# PWR_MGMT.net
KiCad netlist of a schematic drawn in Altium Designer
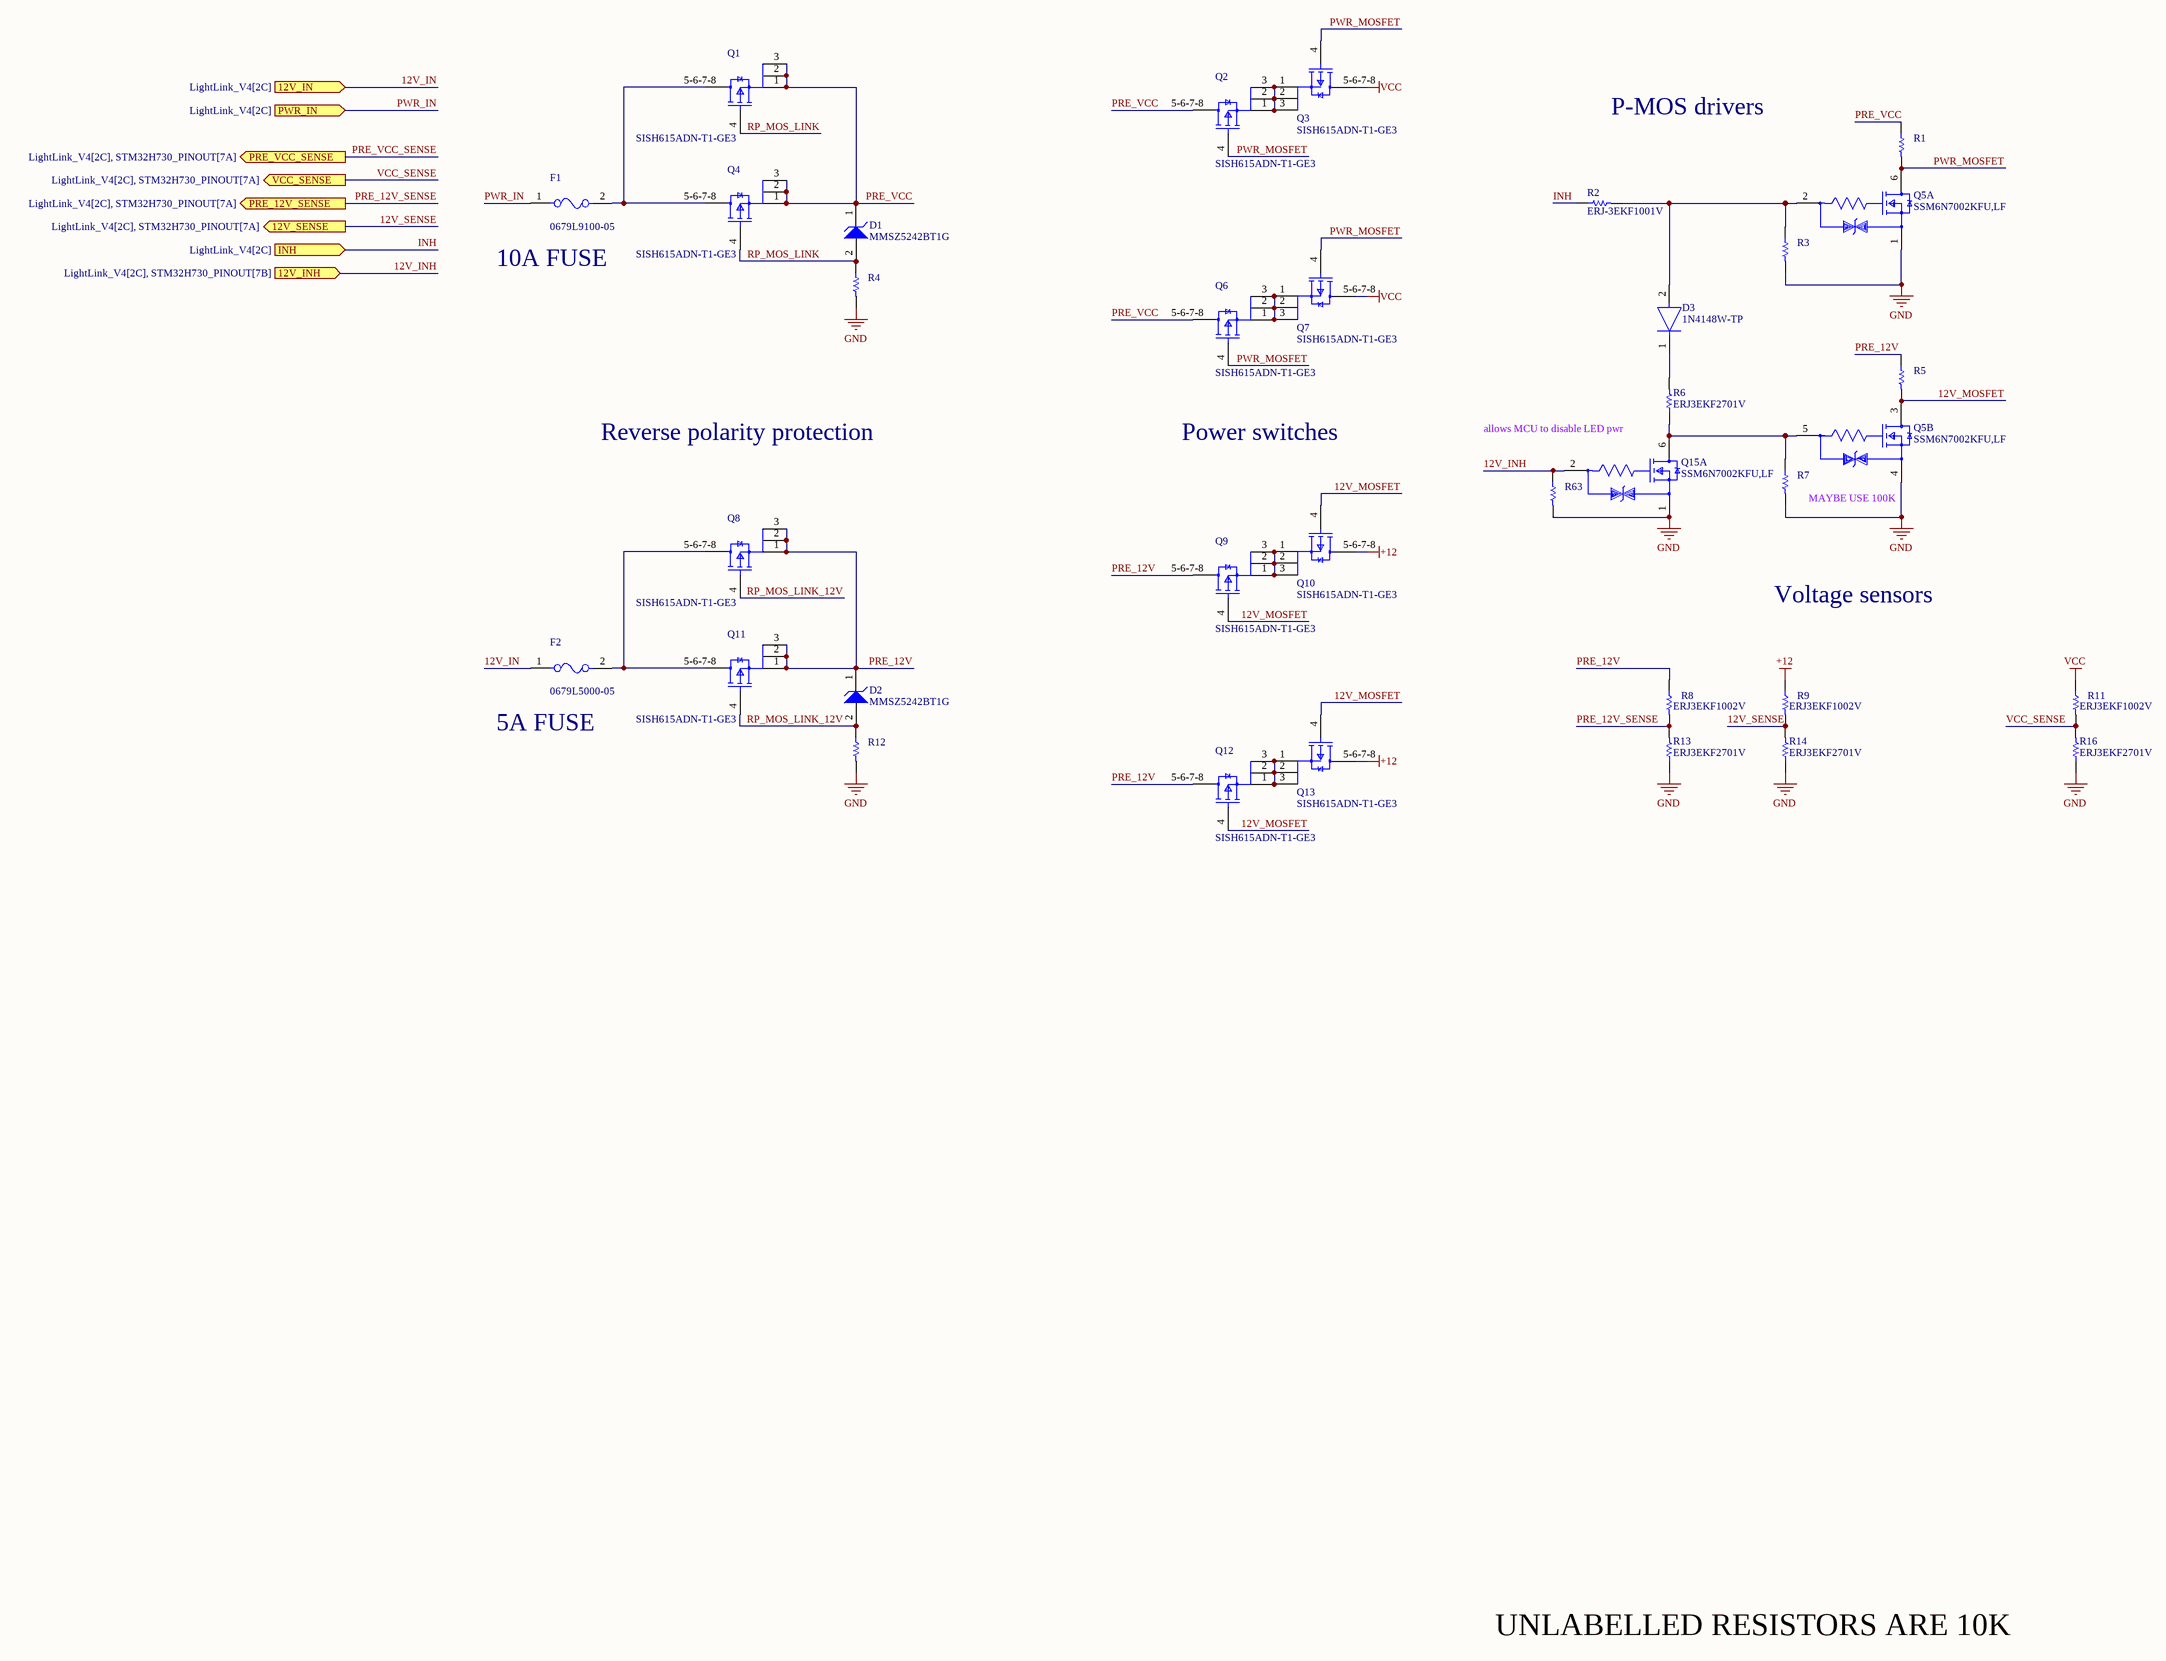
[diagram p0: PWR_MGMT.SchDoc]

(export (version "E")
  (design (tool "Eeschema 10.0.6"))
  (components
    (comp (ref "D1")
      (value "MMSZ5242BT1G")
      (footprint "ONSC-SOD-123-2-425-04_V")
      (description "Zener Voltage Regulator, 500 mW, 2-Pin SOD-123, Pb-Free, Tape and Reel")
      (fields (field (name "MANUFACTURER") "On Semiconductor"))
      (libsource (lib "Altium Content Vault") (part "ONSC-K1A2-2"))
    )
    (comp (ref "D2")
      (value "MMSZ5242BT1G")
      (footprint "ONSC-SOD-123-2-425-04_V")
      (description "Zener Voltage Regulator, 500 mW, 2-Pin SOD-123, Pb-Free, Tape and Reel")
      (fields (field (name "MANUFACTURER") "On Semiconductor"))
      (libsource (lib "Altium Content Vault") (part "ONSC-K1A2-2"))
    )
    (comp (ref "D3")
      (value "1N4148W-TP")
      (footprint "FP-SOD-123-IPC_A")
      (description "DIODE GEN PURP 100V 150MA SOD123")
      (libsource (lib "Altium Content Vault") (part "d7152d700b627762746794eb795d46e"))
    )
    (comp (ref "F1")
      (value "0679L9100-05")
      (footprint "FP-0679L-MFG")
      (description "DIFF P#!!!\r\n\r\nFUSE BRD MNT 10A 125VAC/VDC")
      (fields
        (field (name "OCTOPART") "https://octopart.com/0679l9150-01-bel+fuse-70850665")
        (field (name "MANUFACTURER") "Bel Fuse")
      )
      (libsource (lib "Altium Content Vault") (part "5bcf9b9f640e542cf0359d10258e979"))
    )
    (comp (ref "F2")
      (value "0679L5000-05")
      (footprint "FP-0679L-MFG")
      (description "DIFF P#!!!\r\n\r\nFUSE BRD MNT 5A 125VAC/VDC")
      (fields
        (field (name "OCTOPART") "https://octopart.com/0679l9150-01-bel+fuse-70850665")
        (field (name "MANUFACTURER") "Bel Fuse")
      )
      (libsource (lib "Altium Content Vault") (part "5bcf9b9f640e542cf0359d10258e979"))
    )
    (comp (ref "Q1")
      (value "SISH615ADN-T1-GE3")
      (footprint "SISH615ADN-T1-GE3-Footprint-1")
      (description "Trans MOSFET P-CH 20V 22.1A 8-Pin PowerPAK 1212 EP T/R")
      (libsource (lib "uORocketry Hardware") (part "SISH615ADN-T1-GE3-Symbol-1"))
    )
    (comp (ref "Q2")
      (value "SISH615ADN-T1-GE3")
      (footprint "SISH615ADN-T1-GE3-Footprint-1")
      (description "Trans MOSFET P-CH 20V 22.1A 8-Pin PowerPAK 1212 EP T/R")
      (libsource (lib "uORocketry Hardware") (part "SISH615ADN-T1-GE3-Symbol-1"))
    )
    (comp (ref "Q3")
      (value "SISH615ADN-T1-GE3")
      (footprint "SISH615ADN-T1-GE3-Footprint-1")
      (description "Trans MOSFET P-CH 20V 22.1A 8-Pin PowerPAK 1212 EP T/R")
      (libsource (lib "uORocketry Hardware") (part "SISH615ADN-T1-GE3-Symbol-1"))
    )
    (comp (ref "Q4")
      (value "SISH615ADN-T1-GE3")
      (footprint "SISH615ADN-T1-GE3-Footprint-1")
      (description "Trans MOSFET P-CH 20V 22.1A 8-Pin PowerPAK 1212 EP T/R")
      (libsource (lib "uORocketry Hardware") (part "SISH615ADN-T1-GE3-Symbol-1"))
    )
    (comp (ref "Q5")
      (value "SSM6N7002KFU,LF")
      (footprint "FP-SSOP6-P-0_65A-MFG")
      (description "MOSFET 2N-CH 60V 0.3A")
      (libsource (lib "Altium Content Vault") (part "088aa6ac103fdeebe0d1c52ece6b7b9"))
    )
    (comp (ref "Q6")
      (value "SISH615ADN-T1-GE3")
      (footprint "SISH615ADN-T1-GE3-Footprint-1")
      (description "Trans MOSFET P-CH 20V 22.1A 8-Pin PowerPAK 1212 EP T/R")
      (libsource (lib "uORocketry Hardware") (part "SISH615ADN-T1-GE3-Symbol-1"))
    )
    (comp (ref "Q7")
      (value "SISH615ADN-T1-GE3")
      (footprint "SISH615ADN-T1-GE3-Footprint-1")
      (description "Trans MOSFET P-CH 20V 22.1A 8-Pin PowerPAK 1212 EP T/R")
      (libsource (lib "uORocketry Hardware") (part "SISH615ADN-T1-GE3-Symbol-1"))
    )
    (comp (ref "Q8")
      (value "SISH615ADN-T1-GE3")
      (footprint "SISH615ADN-T1-GE3-Footprint-1")
      (description "Trans MOSFET P-CH 20V 22.1A 8-Pin PowerPAK 1212 EP T/R")
      (libsource (lib "uORocketry Hardware") (part "SISH615ADN-T1-GE3-Symbol-1"))
    )
    (comp (ref "Q9")
      (value "SISH615ADN-T1-GE3")
      (footprint "SISH615ADN-T1-GE3-Footprint-1")
      (description "Trans MOSFET P-CH 20V 22.1A 8-Pin PowerPAK 1212 EP T/R")
      (libsource (lib "uORocketry Hardware") (part "SISH615ADN-T1-GE3-Symbol-1"))
    )
    (comp (ref "Q10")
      (value "SISH615ADN-T1-GE3")
      (footprint "SISH615ADN-T1-GE3-Footprint-1")
      (description "Trans MOSFET P-CH 20V 22.1A 8-Pin PowerPAK 1212 EP T/R")
      (libsource (lib "uORocketry Hardware") (part "SISH615ADN-T1-GE3-Symbol-1"))
    )
    (comp (ref "Q11")
      (value "SISH615ADN-T1-GE3")
      (footprint "SISH615ADN-T1-GE3-Footprint-1")
      (description "Trans MOSFET P-CH 20V 22.1A 8-Pin PowerPAK 1212 EP T/R")
      (libsource (lib "uORocketry Hardware") (part "SISH615ADN-T1-GE3-Symbol-1"))
    )
    (comp (ref "Q12")
      (value "SISH615ADN-T1-GE3")
      (footprint "SISH615ADN-T1-GE3-Footprint-1")
      (description "Trans MOSFET P-CH 20V 22.1A 8-Pin PowerPAK 1212 EP T/R")
      (libsource (lib "uORocketry Hardware") (part "SISH615ADN-T1-GE3-Symbol-1"))
    )
    (comp (ref "Q13")
      (value "SISH615ADN-T1-GE3")
      (footprint "SISH615ADN-T1-GE3-Footprint-1")
      (description "Trans MOSFET P-CH 20V 22.1A 8-Pin PowerPAK 1212 EP T/R")
      (libsource (lib "uORocketry Hardware") (part "SISH615ADN-T1-GE3-Symbol-1"))
    )
    (comp (ref "Q15")
      (value "SSM6N7002KFU,LF")
      (footprint "FP-SSOP6-P-0_65A-MFG")
      (description "MOSFET 2N-CH 60V 0.3A")
      (libsource (lib "Altium Content Vault") (part "088aa6ac103fdeebe0d1c52ece6b7b9"))
    )
    (comp (ref "R1")
      (value "ERJ3EKF1002V")
      (footprint "RESC1609X55X30LL15T15")
      (description "Chip Resistor, 10 KOhm, +/- 1%, 0.1 W, -55 to 155 degC, 0603 (1608 Metric), RoHS, Tape and Reel")
      (fields (field (name "TOLERANCE") "1%") (field (name "MANUFACTURER") "Panasonic"))
      (libsource (lib "Altium Content Vault") (part "RES-2"))
    )
    (comp (ref "R2")
      (value "ERJ-3EKF1001V")
      (footprint "RESC1608X55X30LL15T15")
      (fields (field (name "MANUFACTURER") "Panasonic"))
      (libsource (lib "Altium Content Vault") (part "RES"))
    )
    (comp (ref "R3")
      (value "ERJ3EKF1002V")
      (footprint "RESC1609X55X30LL15T15")
      (description "Chip Resistor, 10 KOhm, +/- 1%, 0.1 W, -55 to 155 degC, 0603 (1608 Metric), RoHS, Tape and Reel")
      (fields (field (name "TOLERANCE") "1%") (field (name "MANUFACTURER") "Panasonic"))
      (libsource (lib "Altium Content Vault") (part "RES-2"))
    )
    (comp (ref "R4")
      (value "ERJ3EKF1002V")
      (footprint "RESC1609X55X30LL15T15")
      (description "Chip Resistor, 10 KOhm, +/- 1%, 0.1 W, -55 to 155 degC, 0603 (1608 Metric), RoHS, Tape and Reel")
      (fields (field (name "TOLERANCE") "1%") (field (name "MANUFACTURER") "Panasonic"))
      (libsource (lib "Altium Content Vault") (part "RES-2"))
    )
    (comp (ref "R5")
      (value "ERJ3EKF1002V")
      (footprint "RESC1609X55X30LL15T15")
      (description "Chip Resistor, 10 KOhm, +/- 1%, 0.1 W, -55 to 155 degC, 0603 (1608 Metric), RoHS, Tape and Reel")
      (fields (field (name "TOLERANCE") "1%") (field (name "MANUFACTURER") "Panasonic"))
      (libsource (lib "Altium Content Vault") (part "RES-2"))
    )
    (comp (ref "R6")
      (value "ERJ3EKF2701V")
      (footprint "RESC1608X55X30LL15T15")
      (fields (field (name "MANUFACTURER") "Panasonic"))
      (libsource (lib "Altium Content Vault") (part "RES"))
    )
    (comp (ref "R7")
      (value "ERJ3EKF1002V")
      (footprint "RESC1609X55X30LL15T15")
      (description "Chip Resistor, 10 KOhm, +/- 1%, 0.1 W, -55 to 155 degC, 0603 (1608 Metric), RoHS, Tape and Reel")
      (fields (field (name "TOLERANCE") "1%") (field (name "MANUFACTURER") "Panasonic"))
      (libsource (lib "Altium Content Vault") (part "RES-2"))
    )
    (comp (ref "R8")
      (value "ERJ3EKF1002V")
      (footprint "RESC1609X55X30LL15T15")
      (description "Chip Resistor, 10 KOhm, +/- 1%, 0.1 W, -55 to 155 degC, 0603 (1608 Metric), RoHS, Tape and Reel")
      (fields (field (name "TOLERANCE") "1%") (field (name "MANUFACTURER") "Panasonic"))
      (libsource (lib "Altium Content Vault") (part "RES-2"))
    )
    (comp (ref "R9")
      (value "ERJ3EKF1002V")
      (footprint "RESC1609X55X30LL15T15")
      (description "Chip Resistor, 10 KOhm, +/- 1%, 0.1 W, -55 to 155 degC, 0603 (1608 Metric), RoHS, Tape and Reel")
      (fields (field (name "TOLERANCE") "1%") (field (name "MANUFACTURER") "Panasonic"))
      (libsource (lib "Altium Content Vault") (part "RES-2"))
    )
    (comp (ref "R11")
      (value "ERJ3EKF1002V")
      (footprint "RESC1609X55X30LL15T15")
      (description "Chip Resistor, 10 KOhm, +/- 1%, 0.1 W, -55 to 155 degC, 0603 (1608 Metric), RoHS, Tape and Reel")
      (fields (field (name "TOLERANCE") "1%") (field (name "MANUFACTURER") "Panasonic"))
      (libsource (lib "Altium Content Vault") (part "RES-2"))
    )
    (comp (ref "R12")
      (value "ERJ3EKF1002V")
      (footprint "RESC1609X55X30LL15T15")
      (description "Chip Resistor, 10 KOhm, +/- 1%, 0.1 W, -55 to 155 degC, 0603 (1608 Metric), RoHS, Tape and Reel")
      (fields (field (name "TOLERANCE") "1%") (field (name "MANUFACTURER") "Panasonic"))
      (libsource (lib "Altium Content Vault") (part "RES-2"))
    )
    (comp (ref "R13")
      (value "ERJ3EKF2701V")
      (footprint "RESC1608X55X30LL15T15")
      (fields (field (name "MANUFACTURER") "Panasonic"))
      (libsource (lib "Altium Content Vault") (part "RES"))
    )
    (comp (ref "R14")
      (value "ERJ3EKF2701V")
      (footprint "RESC1608X55X30LL15T15")
      (fields (field (name "MANUFACTURER") "Panasonic"))
      (libsource (lib "Altium Content Vault") (part "RES"))
    )
    (comp (ref "R16")
      (value "ERJ3EKF2701V")
      (footprint "RESC1608X55X30LL15T15")
      (fields (field (name "MANUFACTURER") "Panasonic"))
      (libsource (lib "Altium Content Vault") (part "RES"))
    )
    (comp (ref "R63")
      (value "ERJ3EKF1002V")
      (footprint "RESC1609X55X30LL15T15")
      (description "Chip Resistor, 10 KOhm, +/- 1%, 0.1 W, -55 to 155 degC, 0603 (1608 Metric), RoHS, Tape and Reel")
      (fields (field (name "TOLERANCE") "1%") (field (name "MANUFACTURER") "Panasonic"))
      (libsource (lib "Altium Content Vault") (part "RES-2"))
    )
  )
  (nets
    (net (code "1") (name "+12") (class "Default")
      (node (ref "Q10") (pin "5-6-7-8") (pinfunction "D_5-6-7-8") (pintype "passive"))
      (node (ref "Q13") (pin "5-6-7-8") (pinfunction "D_5-6-7-8") (pintype "passive"))
      (node (ref "R9") (pin "1") (pinfunction "1_1") (pintype "passive"))
    )
    (net (code "2") (name "/12V_IN") (class "Default")
      (node (ref "F2") (pin "1") (pinfunction "1_1") (pintype "passive"))
    )
    (net (code "3") (name "/12V_INH") (class "Default")
      (node (ref "Q15") (pin "2") (pinfunction "Gate1_2") (pintype "passive"))
      (node (ref "R63") (pin "1") (pinfunction "1_1") (pintype "passive"))
    )
    (net (code "4") (name "/12V_MOSFET") (class "Default")
      (node (ref "Q10") (pin "4") (pinfunction "G_4") (pintype "passive"))
      (node (ref "Q12") (pin "4") (pinfunction "G_4") (pintype "passive"))
      (node (ref "Q13") (pin "4") (pinfunction "G_4") (pintype "passive"))
      (node (ref "Q5") (pin "3") (pinfunction "Drain2_3") (pintype "passive"))
      (node (ref "Q9") (pin "4") (pinfunction "G_4") (pintype "passive"))
      (node (ref "R5") (pin "2") (pinfunction "2_2") (pintype "passive"))
    )
    (net (code "5") (name "/12V_SENSE") (class "Default")
      (node (ref "R14") (pin "2") (pinfunction "2_2") (pintype "passive"))
      (node (ref "R9") (pin "2") (pinfunction "2_2") (pintype "passive"))
    )
    (net (code "6") (name "/INH") (class "Default")
      (node (ref "R2") (pin "1") (pinfunction "1_1") (pintype "passive"))
    )
    (net (code "7") (name "/PRE_12V") (class "Default")
      (node (ref "D2") (pin "1") (pinfunction "K_1") (pintype "passive"))
      (node (ref "Q11") (pin "1") (pinfunction "S_1") (pintype "passive"))
      (node (ref "Q11") (pin "2") (pinfunction "S_2") (pintype "passive"))
      (node (ref "Q11") (pin "3") (pinfunction "S_3") (pintype "passive"))
      (node (ref "Q12") (pin "5-6-7-8") (pinfunction "D_5-6-7-8") (pintype "passive"))
      (node (ref "Q8") (pin "1") (pinfunction "S_1") (pintype "passive"))
      (node (ref "Q8") (pin "2") (pinfunction "S_2") (pintype "passive"))
      (node (ref "Q8") (pin "3") (pinfunction "S_3") (pintype "passive"))
      (node (ref "Q9") (pin "5-6-7-8") (pinfunction "D_5-6-7-8") (pintype "passive"))
      (node (ref "R5") (pin "1") (pinfunction "1_1") (pintype "passive"))
      (node (ref "R8") (pin "1") (pinfunction "1_1") (pintype "passive"))
    )
    (net (code "8") (name "/PRE_12V_SENSE") (class "Default")
      (node (ref "R13") (pin "2") (pinfunction "2_2") (pintype "passive"))
      (node (ref "R8") (pin "2") (pinfunction "2_2") (pintype "passive"))
    )
    (net (code "9") (name "/PRE_VCC") (class "Default")
      (node (ref "D1") (pin "1") (pinfunction "K_1") (pintype "passive"))
      (node (ref "Q1") (pin "1") (pinfunction "S_1") (pintype "passive"))
      (node (ref "Q1") (pin "2") (pinfunction "S_2") (pintype "passive"))
      (node (ref "Q1") (pin "3") (pinfunction "S_3") (pintype "passive"))
      (node (ref "Q2") (pin "5-6-7-8") (pinfunction "D_5-6-7-8") (pintype "passive"))
      (node (ref "Q4") (pin "1") (pinfunction "S_1") (pintype "passive"))
      (node (ref "Q4") (pin "2") (pinfunction "S_2") (pintype "passive"))
      (node (ref "Q4") (pin "3") (pinfunction "S_3") (pintype "passive"))
      (node (ref "Q6") (pin "5-6-7-8") (pinfunction "D_5-6-7-8") (pintype "passive"))
      (node (ref "R1") (pin "1") (pinfunction "1_1") (pintype "passive"))
    )
    (net (code "11") (name "/PWR_IN") (class "Default")
      (node (ref "F1") (pin "1") (pinfunction "1_1") (pintype "passive"))
    )
    (net (code "12") (name "/PWR_MOSFET") (class "Default")
      (node (ref "Q2") (pin "4") (pinfunction "G_4") (pintype "passive"))
      (node (ref "Q3") (pin "4") (pinfunction "G_4") (pintype "passive"))
      (node (ref "Q5") (pin "6") (pinfunction "Drain1_6") (pintype "passive"))
      (node (ref "Q6") (pin "4") (pinfunction "G_4") (pintype "passive"))
      (node (ref "Q7") (pin "4") (pinfunction "G_4") (pintype "passive"))
      (node (ref "R1") (pin "2") (pinfunction "2_2") (pintype "passive"))
    )
    (net (code "13") (name "/RP_MOS_LINK") (class "Default")
      (node (ref "D1") (pin "2") (pinfunction "A_2") (pintype "passive"))
      (node (ref "Q1") (pin "4") (pinfunction "G_4") (pintype "passive"))
      (node (ref "Q4") (pin "4") (pinfunction "G_4") (pintype "passive"))
      (node (ref "R4") (pin "1") (pinfunction "1_1") (pintype "passive"))
    )
    (net (code "14") (name "/RP_MOS_LINK_12V") (class "Default")
      (node (ref "D2") (pin "2") (pinfunction "A_2") (pintype "passive"))
      (node (ref "Q11") (pin "4") (pinfunction "G_4") (pintype "passive"))
      (node (ref "Q8") (pin "4") (pinfunction "G_4") (pintype "passive"))
      (node (ref "R12") (pin "1") (pinfunction "1_1") (pintype "passive"))
    )
    (net (code "15") (name "/VCC_SENSE") (class "Default")
      (node (ref "R11") (pin "2") (pinfunction "2_2") (pintype "passive"))
      (node (ref "R16") (pin "2") (pinfunction "2_2") (pintype "passive"))
    )
    (net (code "16") (name "GND") (class "Default")
      (node (ref "Q15") (pin "1") (pinfunction "Source1_1") (pintype "passive"))
      (node (ref "Q5") (pin "1") (pinfunction "Source1_1") (pintype "passive"))
      (node (ref "Q5") (pin "4") (pinfunction "Source2_4") (pintype "passive"))
      (node (ref "R12") (pin "2") (pinfunction "2_2") (pintype "passive"))
      (node (ref "R13") (pin "1") (pinfunction "1_1") (pintype "passive"))
      (node (ref "R14") (pin "1") (pinfunction "1_1") (pintype "passive"))
      (node (ref "R16") (pin "1") (pinfunction "1_1") (pintype "passive"))
      (node (ref "R3") (pin "2") (pinfunction "2_2") (pintype "passive"))
      (node (ref "R4") (pin "2") (pinfunction "2_2") (pintype "passive"))
      (node (ref "R63") (pin "2") (pinfunction "2_2") (pintype "passive"))
      (node (ref "R7") (pin "2") (pinfunction "2_2") (pintype "passive"))
    )
    (net (code "17") (name "Net-(D3-A)") (class "Default")
      (node (ref "D3") (pin "2") (pinfunction "A_2") (pintype "passive"))
      (node (ref "Q5") (pin "2") (pinfunction "Gate1_2") (pintype "passive"))
      (node (ref "R2") (pin "2") (pinfunction "2_2") (pintype "passive"))
      (node (ref "R3") (pin "1") (pinfunction "1_1") (pintype "passive"))
    )
    (net (code "18") (name "Net-(D3-C)") (class "Default")
      (node (ref "D3") (pin "1") (pinfunction "C_1") (pintype "passive"))
      (node (ref "R6") (pin "2") (pinfunction "2_2") (pintype "passive"))
    )
    (net (code "19") (name "Net-(Q1-D)") (class "Default")
      (node (ref "F1") (pin "2") (pinfunction "2_2") (pintype "passive"))
      (node (ref "Q1") (pin "5-6-7-8") (pinfunction "D_5-6-7-8") (pintype "passive"))
      (node (ref "Q4") (pin "5-6-7-8") (pinfunction "D_5-6-7-8") (pintype "passive"))
    )
    (net (code "20") (name "Net-(Q2-S-Pad1)") (class "Default")
      (node (ref "Q2") (pin "1") (pinfunction "S_1") (pintype "passive"))
      (node (ref "Q2") (pin "2") (pinfunction "S_2") (pintype "passive"))
      (node (ref "Q2") (pin "3") (pinfunction "S_3") (pintype "passive"))
      (node (ref "Q3") (pin "1") (pinfunction "S_1") (pintype "passive"))
      (node (ref "Q3") (pin "2") (pinfunction "S_2") (pintype "passive"))
      (node (ref "Q3") (pin "3") (pinfunction "S_3") (pintype "passive"))
    )
    (net (code "21") (name "Net-(Q6-S-Pad1)") (class "Default")
      (node (ref "Q6") (pin "1") (pinfunction "S_1") (pintype "passive"))
      (node (ref "Q6") (pin "2") (pinfunction "S_2") (pintype "passive"))
      (node (ref "Q6") (pin "3") (pinfunction "S_3") (pintype "passive"))
      (node (ref "Q7") (pin "1") (pinfunction "S_1") (pintype "passive"))
      (node (ref "Q7") (pin "2") (pinfunction "S_2") (pintype "passive"))
      (node (ref "Q7") (pin "3") (pinfunction "S_3") (pintype "passive"))
    )
    (net (code "22") (name "Net-(Q10-S-Pad1)") (class "Default")
      (node (ref "Q10") (pin "1") (pinfunction "S_1") (pintype "passive"))
      (node (ref "Q10") (pin "2") (pinfunction "S_2") (pintype "passive"))
      (node (ref "Q10") (pin "3") (pinfunction "S_3") (pintype "passive"))
      (node (ref "Q9") (pin "1") (pinfunction "S_1") (pintype "passive"))
      (node (ref "Q9") (pin "2") (pinfunction "S_2") (pintype "passive"))
      (node (ref "Q9") (pin "3") (pinfunction "S_3") (pintype "passive"))
    )
    (net (code "23") (name "Net-(Q11-D)") (class "Default")
      (node (ref "F2") (pin "2") (pinfunction "2_2") (pintype "passive"))
      (node (ref "Q11") (pin "5-6-7-8") (pinfunction "D_5-6-7-8") (pintype "passive"))
      (node (ref "Q8") (pin "5-6-7-8") (pinfunction "D_5-6-7-8") (pintype "passive"))
    )
    (net (code "24") (name "Net-(Q12-S-Pad1)") (class "Default")
      (node (ref "Q12") (pin "1") (pinfunction "S_1") (pintype "passive"))
      (node (ref "Q12") (pin "2") (pinfunction "S_2") (pintype "passive"))
      (node (ref "Q12") (pin "3") (pinfunction "S_3") (pintype "passive"))
      (node (ref "Q13") (pin "1") (pinfunction "S_1") (pintype "passive"))
      (node (ref "Q13") (pin "2") (pinfunction "S_2") (pintype "passive"))
      (node (ref "Q13") (pin "3") (pinfunction "S_3") (pintype "passive"))
    )
    (net (code "25") (name "Net-(Q15A-Drain1)") (class "Default")
      (node (ref "Q15") (pin "6") (pinfunction "Drain1_6") (pintype "passive"))
      (node (ref "Q5") (pin "5") (pinfunction "Gate2_5") (pintype "passive"))
      (node (ref "R6") (pin "1") (pinfunction "1_1") (pintype "passive"))
      (node (ref "R7") (pin "1") (pinfunction "1_1") (pintype "passive"))
    )
    (net (code "26") (name "VCC") (class "Default")
      (node (ref "Q3") (pin "5-6-7-8") (pinfunction "D_5-6-7-8") (pintype "passive"))
      (node (ref "Q7") (pin "5-6-7-8") (pinfunction "D_5-6-7-8") (pintype "passive"))
      (node (ref "R11") (pin "1") (pinfunction "1_1") (pintype "passive"))
    )
  )
)
